# Power.net
KiCad netlist of a schematic drawn in Altium Designer
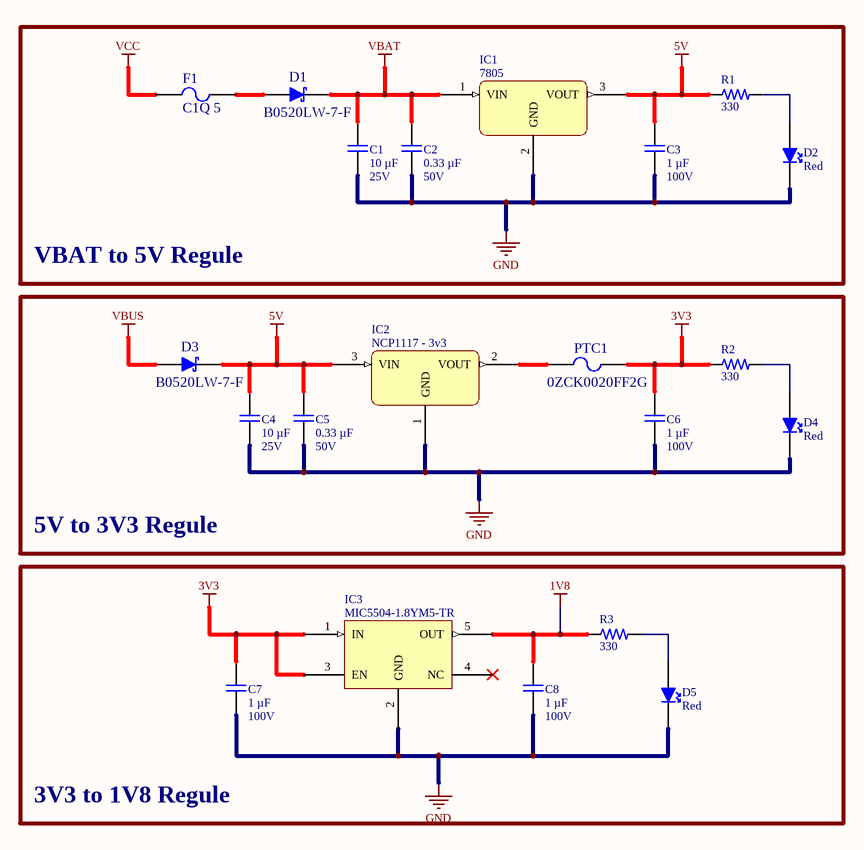
[diagram p0: Power.SchDoc]

(export (version "E")
  (design (tool "Eeschema 10.0.6"))
  (components
    (comp (ref "C1")
      (value "10 µF")
      (footprint "MergenElektronik_Capacitors_Ceramics_SMDs_0603_L_NS")
      (description "Mergen Elektronik - Capacitors - Ceramics - SMDs - 0603 - 10 µF - 25V")
      (fields
        (field (name "MANUFACTURER") "Murata Electronics")
        (field (name "TOLERANCE") "±20%")
        (field (name "VOLTAGE RATING") "25V")
      )
      (libsource (lib "MergenElektronik_Capacitors_Ceramics_SMDs") (part "MergenElektronik_Capacitors_Ceramic_SMDs_10µF_25V"))
    )
    (comp (ref "C2")
      (value "0.33 µF")
      (footprint "MergenElektronik_Capacitors_Ceramics_SMDs_0603_L_NS")
      (description "Mergen Elektronik - Capacitors - Ceramics - SMDs - 0603 - 0.33 µF - 50V")
      (fields
        (field (name "MANUFACTURER") "TDK Corporation")
        (field (name "TOLERANCE") "±10%")
        (field (name "VOLTAGE RATING") "50V")
      )
      (libsource (lib "MergenElektronik_Capacitors_Ceramics_SMDs") (part "MergenElektronik_Capacitors_Ceramic_SMDs_0.33µF_50V"))
    )
    (comp (ref "C3")
      (value "1 µF")
      (footprint "MergenElektronik_Capacitors_Ceramics_SMDs_1206_M_NS")
      (description "Mergen Elektronik - Capacitors - Ceramics - SMDs - 1206 - 1 µF - 100V")
      (fields
        (field (name "MANUFACTURER") "Samsung Electro-Mechanics")
        (field (name "TOLERANCE") "±10%")
        (field (name "VOLTAGE RATING") "100V")
      )
      (libsource (lib "MergenElektronik_Capacitors_Ceramics_SMDs") (part "MergenElektronik_Capacitors_Ceramic_SMDs_1µF_100V"))
    )
    (comp (ref "C4")
      (value "10 µF")
      (footprint "MergenElektronik_Capacitors_Ceramics_SMDs_0603_M_NS")
      (description "Mergen Elektronik - Capacitors - Ceramics - SMDs - 0603 - 10 µF - 25V")
      (fields
        (field (name "MANUFACTURER") "Murata Electronics")
        (field (name "TOLERANCE") "±20%")
        (field (name "VOLTAGE RATING") "25V")
      )
      (libsource (lib "MergenElektronik_Capacitors_Ceramics_SMDs") (part "MergenElektronik_Capacitors_Ceramic_SMDs_10µF_25V"))
    )
    (comp (ref "C5")
      (value "0.33 µF")
      (footprint "MergenElektronik_Capacitors_Ceramics_SMDs_0603_M_NS")
      (description "Mergen Elektronik - Capacitors - Ceramics - SMDs - 0603 - 0.33 µF - 50V")
      (fields
        (field (name "MANUFACTURER") "TDK Corporation")
        (field (name "TOLERANCE") "±10%")
        (field (name "VOLTAGE RATING") "50V")
      )
      (libsource (lib "MergenElektronik_Capacitors_Ceramics_SMDs") (part "MergenElektronik_Capacitors_Ceramic_SMDs_0.33µF_50V"))
    )
    (comp (ref "C6")
      (value "1 µF")
      (footprint "MergenElektronik_Capacitors_Ceramics_SMDs_1206_M_NS")
      (description "Mergen Elektronik - Capacitors - Ceramics - SMDs - 1206 - 1 µF - 100V")
      (fields
        (field (name "MANUFACTURER") "Samsung Electro-Mechanics")
        (field (name "TOLERANCE") "±10%")
        (field (name "VOLTAGE RATING") "100V")
      )
      (libsource (lib "MergenElektronik_Capacitors_Ceramics_SMDs") (part "MergenElektronik_Capacitors_Ceramic_SMDs_1µF_100V"))
    )
    (comp (ref "C7")
      (value "1 µF")
      (footprint "MergenElektronik_Capacitors_Ceramics_SMDs_1206_M_NS")
      (description "Mergen Elektronik - Capacitors - Ceramics - SMDs - 1206 - 1 µF - 100V")
      (fields
        (field (name "MANUFACTURER") "Samsung Electro-Mechanics")
        (field (name "TOLERANCE") "±10%")
        (field (name "VOLTAGE RATING") "100V")
      )
      (libsource (lib "MergenElektronik_Capacitors_Ceramics_SMDs") (part "MergenElektronik_Capacitors_Ceramic_SMDs_1µF_100V"))
    )
    (comp (ref "C8")
      (value "1 µF")
      (footprint "MergenElektronik_Capacitors_Ceramics_SMDs_1206_M_NS")
      (description "Mergen Elektronik - Capacitors - Ceramics - SMDs - 1206 - 1 µF - 100V")
      (fields
        (field (name "MANUFACTURER") "Samsung Electro-Mechanics")
        (field (name "TOLERANCE") "±10%")
        (field (name "VOLTAGE RATING") "100V")
      )
      (libsource (lib "MergenElektronik_Capacitors_Ceramics_SMDs") (part "MergenElektronik_Capacitors_Ceramic_SMDs_1µF_100V"))
    )
    (comp (ref "D1")
      (value "B0520LW-7-F")
      (footprint "MergenElektronik_Diodes_SchottkyDiodes_SOD-523")
      (description "Mergen Elektronik - Diodes - Schottky Diodes - B0520LW-7-F")
      (fields (field (name "MANUFACTURER") "Diodes Incorporated"))
      (libsource (lib "MergenElektronik_Diodes_SchottkyDiodes") (part "MergenElektronik_Diodes_SchottkyDiodes_B0520LW-7-F"))
    )
    (comp (ref "D2")
      (value "Red")
      (footprint "MergenElektronik_Leds_SMDs_0603_M_NS")
      (description "Mergen Elektronik - Leds - SMDs - Red - 0603")
      (fields (field (name "MANUFACTURER") "Würth Elektronik"))
      (libsource (lib "MergenElektronik_Leds_SMDs") (part "MergenElektronik_LEDs_SMDs_Red_0603"))
    )
    (comp (ref "D3")
      (value "B0520LW-7-F")
      (footprint "MergenElektronik_Diodes_SchottkyDiodes_SOD-523")
      (description "Mergen Elektronik - Diodes - Schottky Diodes - B0520LW-7-F")
      (fields (field (name "MANUFACTURER") "Diodes Incorporated"))
      (libsource (lib "MergenElektronik_Diodes_SchottkyDiodes") (part "MergenElektronik_Diodes_SchottkyDiodes_B0520LW-7-F"))
    )
    (comp (ref "D4")
      (value "Red")
      (footprint "MergenElektronik_Leds_SMDs_0603_M_NS")
      (description "Mergen Elektronik - Leds - SMDs - Red - 0603")
      (fields (field (name "MANUFACTURER") "Würth Elektronik"))
      (libsource (lib "MergenElektronik_Leds_SMDs") (part "MergenElektronik_LEDs_SMDs_Red_0603"))
    )
    (comp (ref "D5")
      (value "Red")
      (footprint "MergenElektronik_Leds_SMDs_0603_M_NS")
      (description "Mergen Elektronik - Leds - SMDs - Red - 0603")
      (fields (field (name "MANUFACTURER") "Würth Elektronik"))
      (libsource (lib "MergenElektronik_Leds_SMDs") (part "MergenElektronik_LEDs_SMDs_Red_0603"))
    )
    (comp (ref "F1")
      (value "C1Q 5")
      (footprint "MergenElektronik_CircuitProtections_Fuses_1206_l")
      (description "Mergen Elektronik - Circuit Protections - Fuses - 0C1Q 5")
      (fields (field (name "MANUFACTURER") "Bel Fuse Inc."))
      (libsource (lib "MergenElektronik_CircuitProtections_Fuses") (part "MergenElektronik_CircuitProtections_Fuses_0C1Q 5"))
    )
    (comp (ref "IC1")
      (value "7805")
      (footprint "MergenElektronik_Regulators_Linears_DPAK")
      (description "Mergen Elektronik - Regulators - Linears - MC7805BDTG")
      (fields (field (name "MANUFACTURER") "onsemi"))
      (libsource (lib "MergenElektronik_Regulators_Linears") (part "MergenElektronik_Regulators_Linears_MC7805BDTG"))
    )
    (comp (ref "IC2")
      (value "NCP1117 - 3v3")
      (footprint "MergenElektronik_Regulators_Linears_SOT223")
      (description "Mergen Elektronik - Regulators - Linears - NCP1117ST33T3G")
      (fields (field (name "MANUFACTURER") "onsemi"))
      (libsource (lib "MergenElektronik_Regulators_Linears") (part "MergenElektronik_Regulators_Linears_NCP1117ST33T3G"))
    )
    (comp (ref "IC3")
      (value "MIC5504-1.8YM5-TR")
      (footprint "MergenElektronik_Regulators_Linears_SOT-23-5")
      (description "Mergen Elektronik - Regulators - Linears - MIC5504-1.8YM5-TR")
      (fields (field (name "MANUFACTURER") "Microchip Technology"))
      (libsource (lib "MergenElektronik_Regulators_Linears") (part "MergenElektronik_Regulators_Linears_MIC5504-1.8YM5-TR"))
    )
    (comp (ref "PTC1")
      (value "0ZCK0020FF2G")
      (footprint "MergenElektronik_CircuitProtections_PTCs_0805_M_NS")
      (description "Mergen Elektronik - Circuit Protections - PTCs - 0ZCK0020FF2G")
      (fields (field (name "MANUFACTURER") "Bel Fuse Inc."))
      (libsource (lib "MergenElektronik_CircuitProtections_PTCs") (part "MergenElektronik_CircuitProtections_PTCs_0ZCK0020FF2G"))
    )
    (comp (ref "R1")
      (value "330")
      (footprint "MergenElektronik_Resistors_ChipResistors_0603_M_NS")
      (description "Mergen Elektronik - Resistors - Chip Resistors - 0603 - 330R")
      (fields (field (name "MANUFACTURER") "Stackpole Electronics Inc") (field (name "POWER") "1/10W"))
      (libsource (lib "MergenElektronik_Resistors_ChipResistors") (part "MergenElektronik_Resistors_ChipResistors_0603_330R"))
    )
    (comp (ref "R2")
      (value "330")
      (footprint "MergenElektronik_Resistors_ChipResistors_0603_M_NS")
      (description "Mergen Elektronik - Resistors - Chip Resistors - 0603 - 330R")
      (fields (field (name "MANUFACTURER") "Stackpole Electronics Inc") (field (name "POWER") "1/10W"))
      (libsource (lib "MergenElektronik_Resistors_ChipResistors") (part "MergenElektronik_Resistors_ChipResistors_0603_330R"))
    )
    (comp (ref "R3")
      (value "330")
      (footprint "MergenElektronik_Resistors_ChipResistors_0603_M_NS")
      (description "Mergen Elektronik - Resistors - Chip Resistors - 0603 - 330R")
      (fields (field (name "MANUFACTURER") "Stackpole Electronics Inc") (field (name "POWER") "1/10W"))
      (libsource (lib "MergenElektronik_Resistors_ChipResistors") (part "MergenElektronik_Resistors_ChipResistors_0603_330R"))
    )
  )
  (nets
    (net (code "1") (name "1V8") (class "Default")
      (node (ref "C8") (pin "1") (pinfunction "1_1") (pintype "passive"))
      (node (ref "IC3") (pin "5") (pinfunction "OUT_5") (pintype "output"))
      (node (ref "R3") (pin "1") (pinfunction "1_1") (pintype "passive"))
    )
    (net (code "2") (name "3V3") (class "Default")
      (node (ref "C6") (pin "1") (pinfunction "1_1") (pintype "passive"))
      (node (ref "C7") (pin "1") (pinfunction "1_1") (pintype "passive"))
      (node (ref "IC3") (pin "1") (pinfunction "IN_1") (pintype "input"))
      (node (ref "IC3") (pin "3") (pinfunction "EN_3") (pintype "passive"))
      (node (ref "PTC1") (pin "2") (pinfunction "2_2") (pintype "passive"))
      (node (ref "R2") (pin "1") (pinfunction "1_1") (pintype "passive"))
    )
    (net (code "3") (name "5V") (class "Default")
      (node (ref "C3") (pin "1") (pinfunction "1_1") (pintype "passive"))
      (node (ref "C4") (pin "1") (pinfunction "1_1") (pintype "passive"))
      (node (ref "C5") (pin "1") (pinfunction "1_1") (pintype "passive"))
      (node (ref "D3") (pin "2") (pinfunction "KATOT_2") (pintype "passive"))
      (node (ref "IC1") (pin "3") (pinfunction "VOUT_3") (pintype "output"))
      (node (ref "IC2") (pin "3") (pinfunction "VIN_3") (pintype "input"))
      (node (ref "R1") (pin "1") (pinfunction "1_1") (pintype "passive"))
    )
    (net (code "4") (name "GND") (class "Default")
      (node (ref "C1") (pin "2") (pinfunction "2_2") (pintype "passive"))
      (node (ref "C2") (pin "2") (pinfunction "2_2") (pintype "passive"))
      (node (ref "C3") (pin "2") (pinfunction "2_2") (pintype "passive"))
      (node (ref "C4") (pin "2") (pinfunction "2_2") (pintype "passive"))
      (node (ref "C5") (pin "2") (pinfunction "2_2") (pintype "passive"))
      (node (ref "C6") (pin "2") (pinfunction "2_2") (pintype "passive"))
      (node (ref "C7") (pin "2") (pinfunction "2_2") (pintype "passive"))
      (node (ref "C8") (pin "2") (pinfunction "2_2") (pintype "passive"))
      (node (ref "D2") (pin "2") (pinfunction "KATOT_2") (pintype "passive"))
      (node (ref "D4") (pin "2") (pinfunction "KATOT_2") (pintype "passive"))
      (node (ref "D5") (pin "2") (pinfunction "KATOT_2") (pintype "passive"))
      (node (ref "IC1") (pin "2") (pinfunction "GND_2") (pintype "power_in"))
      (node (ref "IC2") (pin "1") (pinfunction "GND_1") (pintype "power_in"))
      (node (ref "IC3") (pin "2") (pinfunction "GND_2") (pintype "power_in"))
    )
    (net (code "5") (name "Net-(D1-ANOT)") (class "Default")
      (node (ref "D1") (pin "1") (pinfunction "ANOT_1") (pintype "passive"))
      (node (ref "F1") (pin "2") (pinfunction "2_2") (pintype "passive"))
    )
    (net (code "6") (name "Net-(D2-ANOT)") (class "Default")
      (node (ref "D2") (pin "1") (pinfunction "ANOT_1") (pintype "passive"))
      (node (ref "R1") (pin "2") (pinfunction "2_2") (pintype "passive"))
    )
    (net (code "7") (name "Net-(D4-ANOT)") (class "Default")
      (node (ref "D4") (pin "1") (pinfunction "ANOT_1") (pintype "passive"))
      (node (ref "R2") (pin "2") (pinfunction "2_2") (pintype "passive"))
    )
    (net (code "8") (name "Net-(D5-ANOT)") (class "Default")
      (node (ref "D5") (pin "1") (pinfunction "ANOT_1") (pintype "passive"))
      (node (ref "R3") (pin "2") (pinfunction "2_2") (pintype "passive"))
    )
    (net (code "9") (name "Net-(IC2-VOUT)") (class "Default")
      (node (ref "IC2") (pin "2") (pinfunction "VOUT_2") (pintype "output"))
      (node (ref "PTC1") (pin "1") (pinfunction "1_1") (pintype "passive"))
    )
    (net (code "10") (name "VBAT") (class "Default")
      (node (ref "C1") (pin "1") (pinfunction "1_1") (pintype "passive"))
      (node (ref "C2") (pin "1") (pinfunction "1_1") (pintype "passive"))
      (node (ref "D1") (pin "2") (pinfunction "KATOT_2") (pintype "passive"))
      (node (ref "IC1") (pin "1") (pinfunction "VIN_1") (pintype "input"))
    )
    (net (code "11") (name "VBUS") (class "Default")
      (node (ref "D3") (pin "1") (pinfunction "ANOT_1") (pintype "passive"))
    )
    (net (code "12") (name "VCC") (class "Default")
      (node (ref "F1") (pin "1") (pinfunction "1_1") (pintype "passive"))
    )
    (net (code "13") (name "unconnected-(IC3-NC-Pad4)") (class "Default")
      (node (ref "IC3") (pin "4") (pinfunction "NC_4") (pintype "passive+no_connect"))
    )
  )
)
